# LEDWithDriver.net
KiCad netlist of a schematic drawn in EAGLE
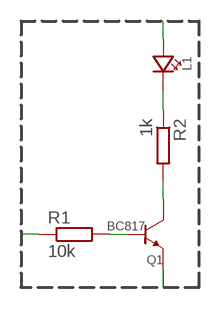
[diagram p0: schematic, sheet 1]

(export (version "E")
  (design (tool "Eeschema 10.0.6"))
  (components
    (comp (ref "L1")
      (value "LED0603")
      (footprint "eagle-import:CHIPLED_0603")
      (libsource (lib "eagle-import") (part "LED0603"))
    )
    (comp (ref "Q1")
      (value "BC817")
      (footprint "eagle-import:SOT23")
      (libsource (lib "eagle-import") (part "TRANSISTOR-NPN-GENERIC-SOT23-BECDEFAULT"))
    )
    (comp (ref "R1")
      (value "10k")
      (footprint "eagle-import:R0603")
      (libsource (lib "eagle-import") (part "R-EU_R0603"))
    )
    (comp (ref "R2")
      (value "1k")
      (footprint "eagle-import:R0603")
      (libsource (lib "eagle-import") (part "R-EU_R0603"))
    )
  )
  (nets
    (net (code "1") (name "Net-(L1-PadC)") (class "Default")
      (node (ref "L1") (pin "C") (pinfunction "C_C") (pintype "bidirectional"))
      (node (ref "R2") (pin "1") (pinfunction "1_1") (pintype "passive"))
    )
    (net (code "2") (name "Net-(Q1-BASE)") (class "Default")
      (node (ref "Q1") (pin "P$1") (pinfunction "BASE_P$1") (pintype "bidirectional"))
      (node (ref "R1") (pin "2") (pinfunction "2_2") (pintype "passive"))
    )
    (net (code "3") (name "Net-(Q1-COLLECTOR)") (class "Default")
      (node (ref "Q1") (pin "P$3") (pinfunction "COLLECTOR_P$3") (pintype "bidirectional"))
      (node (ref "R2") (pin "2") (pinfunction "2_2") (pintype "passive"))
    )
    (net (code "4") (name "unconnected-(L1-PadA)") (class "Default")
      (node (ref "L1") (pin "A") (pinfunction "A_A") (pintype "bidirectional"))
    )
    (net (code "5") (name "unconnected-(Q1-EMITTER-PadP$2)") (class "Default")
      (node (ref "Q1") (pin "P$2") (pinfunction "EMITTER_P$2") (pintype "bidirectional"))
    )
    (net (code "6") (name "unconnected-(R1-Pad1)") (class "Default")
      (node (ref "R1") (pin "1") (pinfunction "1_1") (pintype "passive"))
    )
  )
)
